# 0084_-_Connectors.net
KiCad netlist of a schematic drawn in Altium Designer
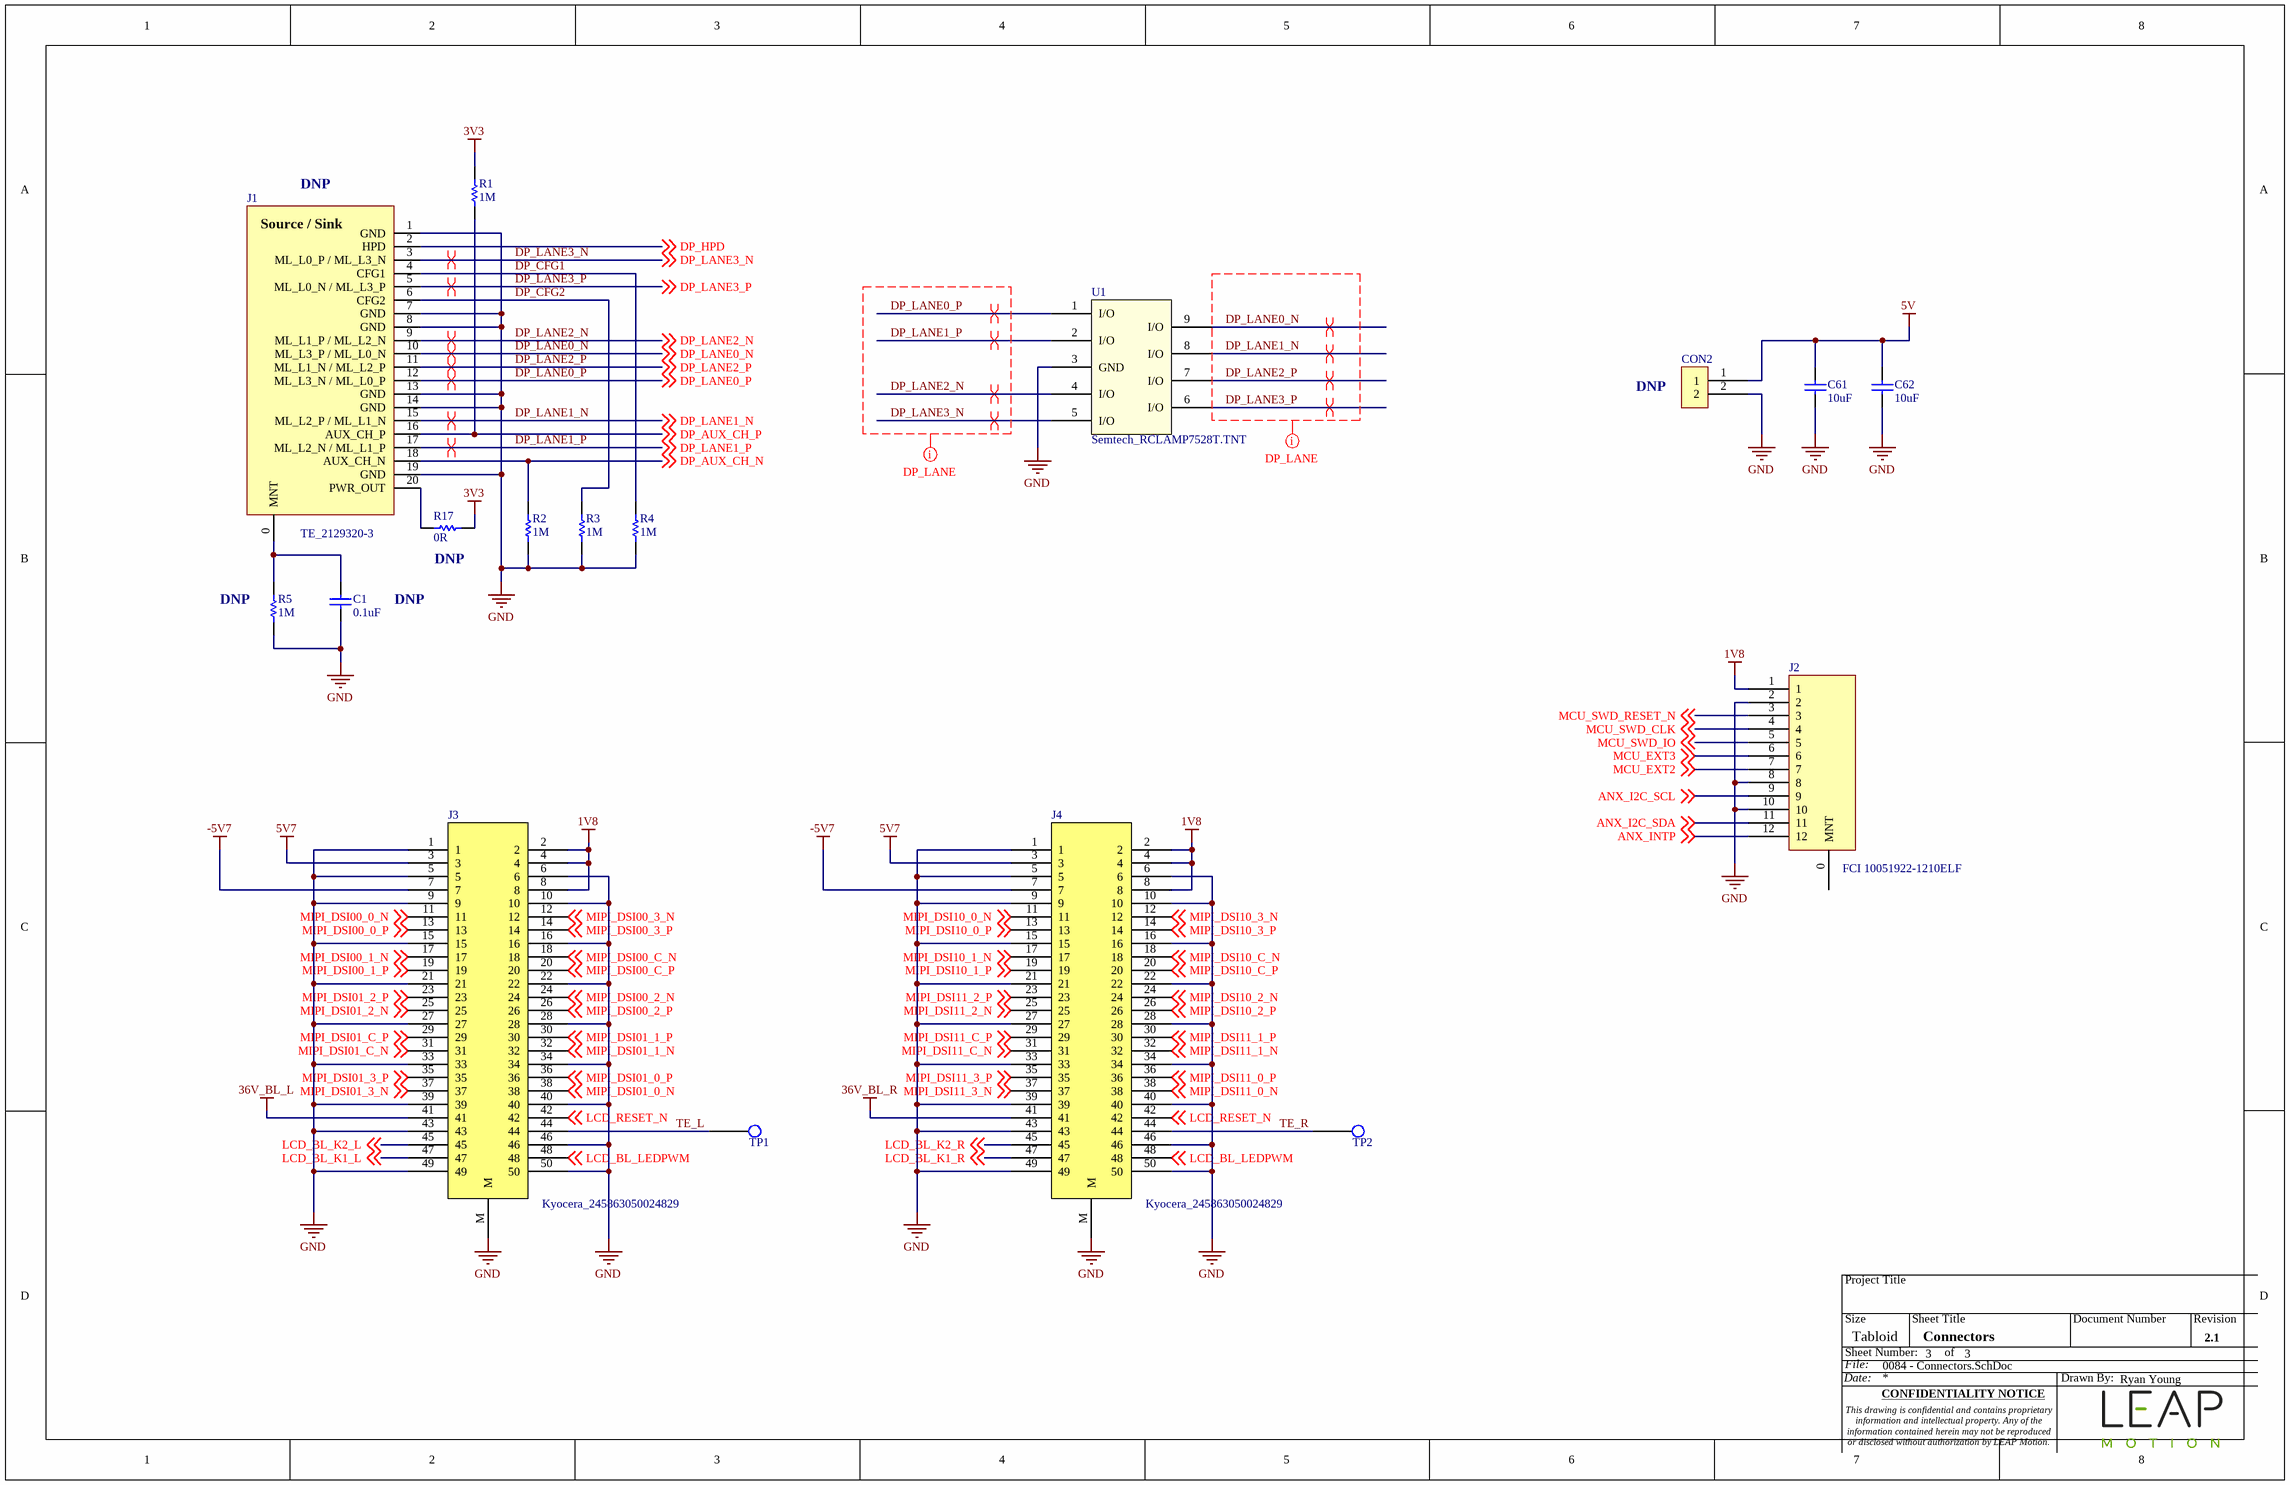
[diagram p0: 0084 - Connectors.SchDoc]

(export (version "E")
  (design (tool "Eeschema 10.0.6"))
  (components
    (comp (ref "C1")
      (value "0.1uF")
      (footprint "CAPC0201(0603)33_N")
      (description "Capacitor, 0.1uF, 10V, 10%, 0201, Ceramic, X5R")
      (fields
        (field (name "MANUFACTURER") "Murata")
        (field (name "TOLERANCE") "10%")
        (field (name "AUTHOR") "AA")
      )
      (libsource (lib "LEAPdb") (part "CAP"))
    )
    (comp (ref "C61")
      (value "10uF")
      (footprint "CAPC1206(3216)170_N")
      (description "Capacitor, 10uF, 50V, 10%, 1206, Ceramic, X7R")
      (fields
        (field (name "MANUFACTURER") "Samsung")
        (field (name "TOLERANCE") "10%")
        (field (name "AUTHOR") "RY")
      )
      (libsource (lib "LEAPdb") (part "CAP"))
    )
    (comp (ref "C62")
      (value "10uF")
      (footprint "CAPC1206(3216)170_N")
      (description "Capacitor, 10uF, 50V, 10%, 1206, Ceramic, X7R")
      (fields
        (field (name "MANUFACTURER") "Samsung")
        (field (name "TOLERANCE") "10%")
        (field (name "AUTHOR") "RY")
      )
      (libsource (lib "LEAPdb") (part "CAP"))
    )
    (comp (ref "CON2")
      (value "CON2")
      (footprint "CON2_100mil")
      (description "Connector, Generic, Header, 2POS, 2.54mm")
      (fields (field (name "MANUFACTURER") "Generic") (field (name "AUTHOR") "JDS"))
      (libsource (lib "LEAPdb") (part "CON2"))
    )
    (comp (ref "J1")
      (value "TE_2129320-3")
      (footprint "TE_2129320-3")
      (description "Connector, TE Connectivity, Receptacle, 20POS, 0.9mm")
      (fields (field (name "MANUFACTURER") "TE Connectivity") (field (name "AUTHOR") "RY"))
      (libsource (lib "LEAPdb") (part "TE_2129320-3"))
    )
    (comp (ref "J2")
      (value "FCI 10051922-1210ELF")
      (footprint "FCI 10051922-1210ELF")
      (description "Connector, FCI, Right Angle, 12POS, 0.5mm")
      (fields (field (name "MANUFACTURER") "FCI") (field (name "AUTHOR") "NR"))
      (libsource (lib "LEAPdb") (part "FCI 10051922-1210ELF"))
    )
    (comp (ref "J3")
      (value "Kyocera_245863050024829")
      (footprint "Kyocera_245863050024829")
      (description "245863050024829")
      (fields (field (name "MANUFACTURER") "Kyocera"))
      (libsource (lib "Kyocera_245863050024829") (part "Kyocera_245863050024829"))
    )
    (comp (ref "J4")
      (value "Kyocera_245863050024829")
      (footprint "Kyocera_245863050024829")
      (description "245863050024829")
      (fields (field (name "MANUFACTURER") "Kyocera"))
      (libsource (lib "Kyocera_245863050024829") (part "Kyocera_245863050024829"))
    )
    (comp (ref "R1")
      (value "1M")
      (footprint "RESC0201(0603)_N")
      (description "Resistor, 1M, 1/20W, 1%, 0201")
      (fields
        (field (name "MANUFACTURER") "Panasonic Electronic Components")
        (field (name "TOLERANCE") "1%")
        (field (name "AUTHOR") "RY")
      )
      (libsource (lib "LEAPdb") (part "RES"))
    )
    (comp (ref "R2")
      (value "1M")
      (footprint "RESC0201(0603)_N")
      (description "Resistor, 1M, 1/20W, 1%, 0201")
      (fields
        (field (name "MANUFACTURER") "Panasonic Electronic Components")
        (field (name "TOLERANCE") "1%")
        (field (name "AUTHOR") "RY")
      )
      (libsource (lib "LEAPdb") (part "RES"))
    )
    (comp (ref "R3")
      (value "1M")
      (footprint "RESC0201(0603)_N")
      (description "Resistor, 1M, 1/20W, 1%, 0201")
      (fields
        (field (name "MANUFACTURER") "Panasonic Electronic Components")
        (field (name "TOLERANCE") "1%")
        (field (name "AUTHOR") "RY")
      )
      (libsource (lib "LEAPdb") (part "RES"))
    )
    (comp (ref "R4")
      (value "1M")
      (footprint "RESC0201(0603)_N")
      (description "Resistor, 1M, 1/20W, 1%, 0201")
      (fields
        (field (name "MANUFACTURER") "Panasonic Electronic Components")
        (field (name "TOLERANCE") "1%")
        (field (name "AUTHOR") "RY")
      )
      (libsource (lib "LEAPdb") (part "RES"))
    )
    (comp (ref "R5")
      (value "1M")
      (footprint "RESC0201(0603)_N")
      (description "Resistor, 1M, 1/20W, 1%, 0201")
      (fields
        (field (name "MANUFACTURER") "Panasonic Electronic Components")
        (field (name "TOLERANCE") "1%")
        (field (name "AUTHOR") "RY")
      )
      (libsource (lib "LEAPdb") (part "RES"))
    )
    (comp (ref "R17")
      (value "0R")
      (footprint "RESC0402(1005)_N")
      (description "Resistor, 0R, 1/10W, Jumper, 0402")
      (fields
        (field (name "MANUFACTURER") "Panasonic Electronic Components")
        (field (name "TOLERANCE") "Jumper")
        (field (name "AUTHOR") "NR")
      )
      (libsource (lib "LEAPdb") (part "RES"))
    )
    (comp (ref "TP1")
      (value "TestPoint")
      (footprint "TestPointRnd-1_5mm")
      (description "Misc, TestPoint")
      (fields (field (name "AUTHOR") "RY"))
      (libsource (lib "LEAPdb") (part "TestPoint"))
    )
    (comp (ref "TP2")
      (value "TestPoint")
      (footprint "TestPointRnd-1_5mm")
      (description "Misc, TestPoint")
      (fields (field (name "AUTHOR") "RY"))
      (libsource (lib "LEAPdb") (part "TestPoint"))
    )
    (comp (ref "U1")
      (value "Semtech_RCLAMP7528T.TNT")
      (footprint "Semtech_RCLAMP7528T.TNT")
      (description "TVS DIODE 5VWM 15VC SLP2611N9T")
      (fields (field (name "MANUFACTURER") "Semtech") (field (name "AUTHOR") "RY"))
      (libsource (lib "LEAPdb") (part "Semtech_RCLAMP7528T.TNT"))
    )
  )
  (nets
    (net (code "1") (name "-5V7") (class "Default")
      (node (ref "J3") (pin "7") (pinfunction "7_7") (pintype "passive"))
      (node (ref "J4") (pin "7") (pinfunction "7_7") (pintype "passive"))
    )
    (net (code "2") (name "/DP_CFG1") (class "Default")
      (node (ref "J1") (pin "4") (pinfunction "CFG1_4") (pintype "passive"))
      (node (ref "R4") (pin "2") (pinfunction "2_2") (pintype "passive"))
    )
    (net (code "3") (name "/DP_CFG2") (class "Default")
      (node (ref "J1") (pin "6") (pinfunction "CFG2_6") (pintype "passive"))
      (node (ref "R3") (pin "2") (pinfunction "2_2") (pintype "passive"))
    )
    (net (code "4") (name "/TE_L") (class "Default")
      (node (ref "J3") (pin "44") (pinfunction "44_44") (pintype "passive"))
      (node (ref "TP1") (pin "0") (pinfunction "0_0") (pintype "power_in"))
    )
    (net (code "5") (name "/TE_R") (class "Default")
      (node (ref "J4") (pin "44") (pinfunction "44_44") (pintype "passive"))
      (node (ref "TP2") (pin "0") (pinfunction "0_0") (pintype "power_in"))
    )
    (net (code "6") (name "1V8") (class "Default")
      (node (ref "J2") (pin "1") (pinfunction "1_1") (pintype "passive"))
      (node (ref "J3") (pin "2") (pinfunction "2_2") (pintype "passive"))
      (node (ref "J3") (pin "4") (pinfunction "4_4") (pintype "passive"))
      (node (ref "J3") (pin "8") (pinfunction "8_8") (pintype "passive"))
      (node (ref "J4") (pin "2") (pinfunction "2_2") (pintype "passive"))
      (node (ref "J4") (pin "4") (pinfunction "4_4") (pintype "passive"))
      (node (ref "J4") (pin "8") (pinfunction "8_8") (pintype "passive"))
    )
    (net (code "7") (name "3V3") (class "Default")
      (node (ref "R1") (pin "2") (pinfunction "2_2") (pintype "passive"))
      (node (ref "R17") (pin "2") (pinfunction "2_2") (pintype "passive"))
    )
    (net (code "8") (name "5V") (class "Default")
      (node (ref "C61") (pin "2") (pinfunction "2_2") (pintype "passive"))
      (node (ref "C62") (pin "2") (pinfunction "2_2") (pintype "passive"))
      (node (ref "CON2") (pin "1") (pinfunction "1_1") (pintype "passive"))
    )
    (net (code "9") (name "5V7") (class "Default")
      (node (ref "J3") (pin "3") (pinfunction "3_3") (pintype "passive"))
      (node (ref "J4") (pin "3") (pinfunction "3_3") (pintype "passive"))
    )
    (net (code "10") (name "36V_BL_L") (class "Default")
      (node (ref "J3") (pin "41") (pinfunction "41_41") (pintype "passive"))
    )
    (net (code "11") (name "36V_BL_R") (class "Default")
      (node (ref "J4") (pin "41") (pinfunction "41_41") (pintype "passive"))
    )
    (net (code "12") (name "ANX_I2C_SCL") (class "Default")
      (node (ref "J2") (pin "9") (pinfunction "9_9") (pintype "passive"))
    )
    (net (code "13") (name "ANX_I2C_SDA") (class "Default")
      (node (ref "J2") (pin "11") (pinfunction "11_11") (pintype "passive"))
    )
    (net (code "14") (name "ANX_INTP") (class "Default")
      (node (ref "J2") (pin "12") (pinfunction "12_12") (pintype "passive"))
    )
    (net (code "15") (name "DP_AUX_CH_N") (class "Default")
      (node (ref "J1") (pin "18") (pinfunction "AUX_CH_N_18") (pintype "passive"))
      (node (ref "R2") (pin "2") (pinfunction "2_2") (pintype "passive"))
    )
    (net (code "16") (name "DP_AUX_CH_P") (class "Default")
      (node (ref "J1") (pin "16") (pinfunction "AUX_CH_P_16") (pintype "passive"))
      (node (ref "R1") (pin "1") (pinfunction "1_1") (pintype "passive"))
    )
    (net (code "17") (name "DP_HPD") (class "Default")
      (node (ref "J1") (pin "2") (pinfunction "HPD_2") (pintype "passive"))
    )
    (net (code "18") (name "DP_LANE0_N") (class "Default")
      (node (ref "J1") (pin "10") (pinfunction "ML_L3_P_/_ML_L0_N_10") (pintype "passive"))
      (node (ref "U1") (pin "9") (pinfunction "I/O_9") (pintype "passive"))
    )
    (net (code "19") (name "DP_LANE0_P") (class "Default")
      (node (ref "J1") (pin "12") (pinfunction "ML_L3_N_/_ML_L0_P_12") (pintype "passive"))
      (node (ref "U1") (pin "1") (pinfunction "I/O_1") (pintype "passive"))
    )
    (net (code "20") (name "DP_LANE1_N") (class "Default")
      (node (ref "J1") (pin "15") (pinfunction "ML_L2_P_/_ML_L1_N_15") (pintype "passive"))
      (node (ref "U1") (pin "8") (pinfunction "I/O_8") (pintype "passive"))
    )
    (net (code "21") (name "DP_LANE1_P") (class "Default")
      (node (ref "J1") (pin "17") (pinfunction "ML_L2_N_/_ML_L1_P_17") (pintype "passive"))
      (node (ref "U1") (pin "2") (pinfunction "I/O_2") (pintype "passive"))
    )
    (net (code "22") (name "DP_LANE2_N") (class "Default")
      (node (ref "J1") (pin "9") (pinfunction "ML_L1_P_/_ML_L2_N_9") (pintype "passive"))
      (node (ref "U1") (pin "4") (pinfunction "I/O_4") (pintype "passive"))
    )
    (net (code "23") (name "DP_LANE2_P") (class "Default")
      (node (ref "J1") (pin "11") (pinfunction "ML_L1_N_/_ML_L2_P_11") (pintype "passive"))
      (node (ref "U1") (pin "7") (pinfunction "I/O_7") (pintype "passive"))
    )
    (net (code "24") (name "DP_LANE3_N") (class "Default")
      (node (ref "J1") (pin "3") (pinfunction "ML_L0_P_/_ML_L3_N_3") (pintype "passive"))
      (node (ref "U1") (pin "5") (pinfunction "I/O_5") (pintype "passive"))
    )
    (net (code "25") (name "DP_LANE3_P") (class "Default")
      (node (ref "J1") (pin "5") (pinfunction "ML_L0_N_/_ML_L3_P_5") (pintype "passive"))
      (node (ref "U1") (pin "6") (pinfunction "I/O_6") (pintype "passive"))
    )
    (net (code "26") (name "GND") (class "Default")
      (node (ref "C1") (pin "1") (pinfunction "1_1") (pintype "passive"))
      (node (ref "C61") (pin "1") (pinfunction "1_1") (pintype "passive"))
      (node (ref "C62") (pin "1") (pinfunction "1_1") (pintype "passive"))
      (node (ref "CON2") (pin "2") (pinfunction "2_2") (pintype "passive"))
      (node (ref "J1") (pin "1") (pinfunction "GND_1") (pintype "passive"))
      (node (ref "J1") (pin "13") (pinfunction "GND_13") (pintype "passive"))
      (node (ref "J1") (pin "14") (pinfunction "GND_14") (pintype "passive"))
      (node (ref "J1") (pin "19") (pinfunction "GND_19") (pintype "passive"))
      (node (ref "J1") (pin "7") (pinfunction "GND_7") (pintype "passive"))
      (node (ref "J1") (pin "8") (pinfunction "GND_8") (pintype "passive"))
      (node (ref "J2") (pin "10") (pinfunction "10_10") (pintype "passive"))
      (node (ref "J2") (pin "2") (pinfunction "2_2") (pintype "passive"))
      (node (ref "J2") (pin "8") (pinfunction "8_8") (pintype "passive"))
      (node (ref "J3") (pin "1") (pinfunction "1_1") (pintype "passive"))
      (node (ref "J3") (pin "10") (pinfunction "10_10") (pintype "passive"))
      (node (ref "J3") (pin "15") (pinfunction "15_15") (pintype "passive"))
      (node (ref "J3") (pin "16") (pinfunction "16_16") (pintype "passive"))
      (node (ref "J3") (pin "21") (pinfunction "21_21") (pintype "passive"))
      (node (ref "J3") (pin "22") (pinfunction "22_22") (pintype "passive"))
      (node (ref "J3") (pin "27") (pinfunction "27_27") (pintype "passive"))
      (node (ref "J3") (pin "28") (pinfunction "28_28") (pintype "passive"))
      (node (ref "J3") (pin "33") (pinfunction "33_33") (pintype "passive"))
      (node (ref "J3") (pin "34") (pinfunction "34_34") (pintype "passive"))
      (node (ref "J3") (pin "39") (pinfunction "39_39") (pintype "passive"))
      (node (ref "J3") (pin "40") (pinfunction "40_40") (pintype "passive"))
      (node (ref "J3") (pin "43") (pinfunction "43_43") (pintype "passive"))
      (node (ref "J3") (pin "46") (pinfunction "46_46") (pintype "passive"))
      (node (ref "J3") (pin "49") (pinfunction "49_49") (pintype "passive"))
      (node (ref "J3") (pin "5") (pinfunction "5_5") (pintype "passive"))
      (node (ref "J3") (pin "50") (pinfunction "50_50") (pintype "passive"))
      (node (ref "J3") (pin "6") (pinfunction "6_6") (pintype "passive"))
      (node (ref "J3") (pin "9") (pinfunction "9_9") (pintype "passive"))
      (node (ref "J3") (pin "M") (pinfunction "M_M") (pintype "passive"))
      (node (ref "J4") (pin "1") (pinfunction "1_1") (pintype "passive"))
      (node (ref "J4") (pin "10") (pinfunction "10_10") (pintype "passive"))
      (node (ref "J4") (pin "15") (pinfunction "15_15") (pintype "passive"))
      (node (ref "J4") (pin "16") (pinfunction "16_16") (pintype "passive"))
      (node (ref "J4") (pin "21") (pinfunction "21_21") (pintype "passive"))
      (node (ref "J4") (pin "22") (pinfunction "22_22") (pintype "passive"))
      (node (ref "J4") (pin "27") (pinfunction "27_27") (pintype "passive"))
      (node (ref "J4") (pin "28") (pinfunction "28_28") (pintype "passive"))
      (node (ref "J4") (pin "33") (pinfunction "33_33") (pintype "passive"))
      (node (ref "J4") (pin "34") (pinfunction "34_34") (pintype "passive"))
      (node (ref "J4") (pin "39") (pinfunction "39_39") (pintype "passive"))
      (node (ref "J4") (pin "40") (pinfunction "40_40") (pintype "passive"))
      (node (ref "J4") (pin "43") (pinfunction "43_43") (pintype "passive"))
      (node (ref "J4") (pin "46") (pinfunction "46_46") (pintype "passive"))
      (node (ref "J4") (pin "49") (pinfunction "49_49") (pintype "passive"))
      (node (ref "J4") (pin "5") (pinfunction "5_5") (pintype "passive"))
      (node (ref "J4") (pin "50") (pinfunction "50_50") (pintype "passive"))
      (node (ref "J4") (pin "6") (pinfunction "6_6") (pintype "passive"))
      (node (ref "J4") (pin "9") (pinfunction "9_9") (pintype "passive"))
      (node (ref "J4") (pin "M") (pinfunction "M_M") (pintype "passive"))
      (node (ref "R2") (pin "1") (pinfunction "1_1") (pintype "passive"))
      (node (ref "R3") (pin "1") (pinfunction "1_1") (pintype "passive"))
      (node (ref "R4") (pin "1") (pinfunction "1_1") (pintype "passive"))
      (node (ref "R5") (pin "1") (pinfunction "1_1") (pintype "passive"))
      (node (ref "U1") (pin "3") (pinfunction "GND_3") (pintype "passive"))
    )
    (net (code "27") (name "LCD_BL_K1_L") (class "Default")
      (node (ref "J3") (pin "47") (pinfunction "47_47") (pintype "passive"))
    )
    (net (code "28") (name "LCD_BL_K1_R") (class "Default")
      (node (ref "J4") (pin "47") (pinfunction "47_47") (pintype "passive"))
    )
    (net (code "29") (name "LCD_BL_K2_L") (class "Default")
      (node (ref "J3") (pin "45") (pinfunction "45_45") (pintype "passive"))
    )
    (net (code "30") (name "LCD_BL_K2_R") (class "Default")
      (node (ref "J4") (pin "45") (pinfunction "45_45") (pintype "passive"))
    )
    (net (code "31") (name "LCD_BL_LEDPWM") (class "Default")
      (node (ref "J3") (pin "48") (pinfunction "48_48") (pintype "passive"))
      (node (ref "J4") (pin "48") (pinfunction "48_48") (pintype "passive"))
    )
    (net (code "32") (name "LCD_RESET_N") (class "Default")
      (node (ref "J3") (pin "42") (pinfunction "42_42") (pintype "passive"))
      (node (ref "J4") (pin "42") (pinfunction "42_42") (pintype "passive"))
    )
    (net (code "33") (name "MCU_EXT2") (class "Default")
      (node (ref "J2") (pin "7") (pinfunction "7_7") (pintype "passive"))
    )
    (net (code "34") (name "MCU_EXT3") (class "Default")
      (node (ref "J2") (pin "6") (pinfunction "6_6") (pintype "passive"))
    )
    (net (code "35") (name "MCU_SWD_CLK") (class "Default")
      (node (ref "J2") (pin "4") (pinfunction "4_4") (pintype "passive"))
    )
    (net (code "36") (name "MCU_SWD_IO") (class "Default")
      (node (ref "J2") (pin "5") (pinfunction "5_5") (pintype "passive"))
    )
    (net (code "37") (name "MCU_SWD_RESET_N") (class "Default")
      (node (ref "J2") (pin "3") (pinfunction "3_3") (pintype "passive"))
    )
    (net (code "38") (name "MIPI_DSI00_0_N") (class "Default")
      (node (ref "J3") (pin "11") (pinfunction "11_11") (pintype "passive"))
    )
    (net (code "39") (name "MIPI_DSI00_0_P") (class "Default")
      (node (ref "J3") (pin "13") (pinfunction "13_13") (pintype "passive"))
    )
    (net (code "40") (name "MIPI_DSI00_1_N") (class "Default")
      (node (ref "J3") (pin "17") (pinfunction "17_17") (pintype "passive"))
    )
    (net (code "41") (name "MIPI_DSI00_1_P") (class "Default")
      (node (ref "J3") (pin "19") (pinfunction "19_19") (pintype "passive"))
    )
    (net (code "42") (name "MIPI_DSI00_2_N") (class "Default")
      (node (ref "J3") (pin "24") (pinfunction "24_24") (pintype "passive"))
    )
    (net (code "43") (name "MIPI_DSI00_2_P") (class "Default")
      (node (ref "J3") (pin "26") (pinfunction "26_26") (pintype "passive"))
    )
    (net (code "44") (name "MIPI_DSI00_3_N") (class "Default")
      (node (ref "J3") (pin "12") (pinfunction "12_12") (pintype "passive"))
    )
    (net (code "45") (name "MIPI_DSI00_3_P") (class "Default")
      (node (ref "J3") (pin "14") (pinfunction "14_14") (pintype "passive"))
    )
    (net (code "46") (name "MIPI_DSI00_C_N") (class "Default")
      (node (ref "J3") (pin "18") (pinfunction "18_18") (pintype "passive"))
    )
    (net (code "47") (name "MIPI_DSI00_C_P") (class "Default")
      (node (ref "J3") (pin "20") (pinfunction "20_20") (pintype "passive"))
    )
    (net (code "48") (name "MIPI_DSI01_0_N") (class "Default")
      (node (ref "J3") (pin "38") (pinfunction "38_38") (pintype "passive"))
    )
    (net (code "49") (name "MIPI_DSI01_0_P") (class "Default")
      (node (ref "J3") (pin "36") (pinfunction "36_36") (pintype "passive"))
    )
    (net (code "50") (name "MIPI_DSI01_1_N") (class "Default")
      (node (ref "J3") (pin "32") (pinfunction "32_32") (pintype "passive"))
    )
    (net (code "51") (name "MIPI_DSI01_1_P") (class "Default")
      (node (ref "J3") (pin "30") (pinfunction "30_30") (pintype "passive"))
    )
    (net (code "52") (name "MIPI_DSI01_2_N") (class "Default")
      (node (ref "J3") (pin "25") (pinfunction "25_25") (pintype "passive"))
    )
    (net (code "53") (name "MIPI_DSI01_2_P") (class "Default")
      (node (ref "J3") (pin "23") (pinfunction "23_23") (pintype "passive"))
    )
    (net (code "54") (name "MIPI_DSI01_3_N") (class "Default")
      (node (ref "J3") (pin "37") (pinfunction "37_37") (pintype "passive"))
    )
    (net (code "55") (name "MIPI_DSI01_3_P") (class "Default")
      (node (ref "J3") (pin "35") (pinfunction "35_35") (pintype "passive"))
    )
    (net (code "56") (name "MIPI_DSI01_C_N") (class "Default")
      (node (ref "J3") (pin "31") (pinfunction "31_31") (pintype "passive"))
    )
    (net (code "57") (name "MIPI_DSI01_C_P") (class "Default")
      (node (ref "J3") (pin "29") (pinfunction "29_29") (pintype "passive"))
    )
    (net (code "58") (name "MIPI_DSI10_0_N") (class "Default")
      (node (ref "J4") (pin "11") (pinfunction "11_11") (pintype "passive"))
    )
    (net (code "59") (name "MIPI_DSI10_0_P") (class "Default")
      (node (ref "J4") (pin "13") (pinfunction "13_13") (pintype "passive"))
    )
    (net (code "60") (name "MIPI_DSI10_1_N") (class "Default")
      (node (ref "J4") (pin "17") (pinfunction "17_17") (pintype "passive"))
    )
    (net (code "61") (name "MIPI_DSI10_1_P") (class "Default")
      (node (ref "J4") (pin "19") (pinfunction "19_19") (pintype "passive"))
    )
    (net (code "62") (name "MIPI_DSI10_2_N") (class "Default")
      (node (ref "J4") (pin "24") (pinfunction "24_24") (pintype "passive"))
    )
    (net (code "63") (name "MIPI_DSI10_2_P") (class "Default")
      (node (ref "J4") (pin "26") (pinfunction "26_26") (pintype "passive"))
    )
    (net (code "64") (name "MIPI_DSI10_3_N") (class "Default")
      (node (ref "J4") (pin "12") (pinfunction "12_12") (pintype "passive"))
    )
    (net (code "65") (name "MIPI_DSI10_3_P") (class "Default")
      (node (ref "J4") (pin "14") (pinfunction "14_14") (pintype "passive"))
    )
    (net (code "66") (name "MIPI_DSI10_C_N") (class "Default")
      (node (ref "J4") (pin "18") (pinfunction "18_18") (pintype "passive"))
    )
    (net (code "67") (name "MIPI_DSI10_C_P") (class "Default")
      (node (ref "J4") (pin "20") (pinfunction "20_20") (pintype "passive"))
    )
    (net (code "68") (name "MIPI_DSI11_0_N") (class "Default")
      (node (ref "J4") (pin "38") (pinfunction "38_38") (pintype "passive"))
    )
    (net (code "69") (name "MIPI_DSI11_0_P") (class "Default")
      (node (ref "J4") (pin "36") (pinfunction "36_36") (pintype "passive"))
    )
    (net (code "70") (name "MIPI_DSI11_1_N") (class "Default")
      (node (ref "J4") (pin "32") (pinfunction "32_32") (pintype "passive"))
    )
    (net (code "71") (name "MIPI_DSI11_1_P") (class "Default")
      (node (ref "J4") (pin "30") (pinfunction "30_30") (pintype "passive"))
    )
    (net (code "72") (name "MIPI_DSI11_2_N") (class "Default")
      (node (ref "J4") (pin "25") (pinfunction "25_25") (pintype "passive"))
    )
    (net (code "73") (name "MIPI_DSI11_2_P") (class "Default")
      (node (ref "J4") (pin "23") (pinfunction "23_23") (pintype "passive"))
    )
    (net (code "74") (name "MIPI_DSI11_3_N") (class "Default")
      (node (ref "J4") (pin "37") (pinfunction "37_37") (pintype "passive"))
    )
    (net (code "75") (name "MIPI_DSI11_3_P") (class "Default")
      (node (ref "J4") (pin "35") (pinfunction "35_35") (pintype "passive"))
    )
    (net (code "76") (name "MIPI_DSI11_C_N") (class "Default")
      (node (ref "J4") (pin "31") (pinfunction "31_31") (pintype "passive"))
    )
    (net (code "77") (name "MIPI_DSI11_C_P") (class "Default")
      (node (ref "J4") (pin "29") (pinfunction "29_29") (pintype "passive"))
    )
    (net (code "78") (name "Net-(J1-MNT)") (class "Default")
      (node (ref "C1") (pin "2") (pinfunction "2_2") (pintype "passive"))
      (node (ref "J1") (pin "0") (pinfunction "MNT_0") (pintype "passive"))
      (node (ref "R5") (pin "2") (pinfunction "2_2") (pintype "passive"))
    )
    (net (code "79") (name "Net-(J1-PWR_OUT)") (class "Default")
      (node (ref "J1") (pin "20") (pinfunction "PWR_OUT_20") (pintype "passive"))
      (node (ref "R17") (pin "1") (pinfunction "1_1") (pintype "passive"))
    )
    (net (code "80") (name "unconnected-(J2-MNT-Pad0)") (class "Default")
      (node (ref "J2") (pin "0") (pinfunction "MNT_0") (pintype "passive"))
    )
  )
)
